# GRLV_double_Rail_v0_2b_P1.net
KiCad netlist of a schematic drawn in Altium Designer
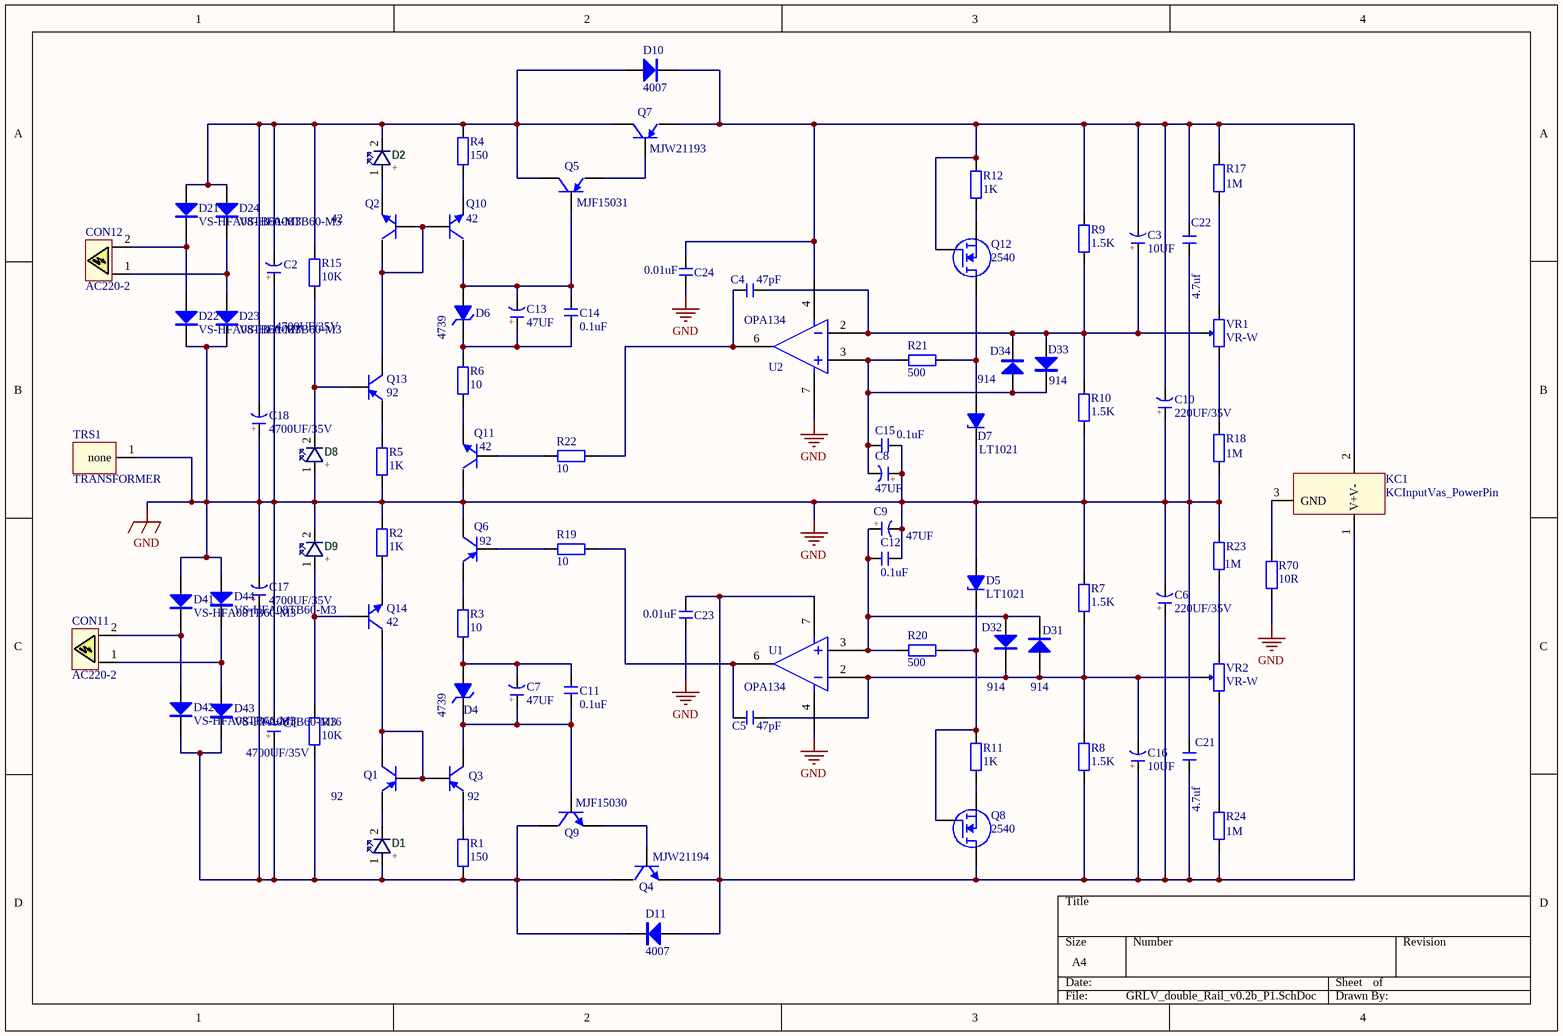
[diagram p0: GRLV_double_Rail_v0.2b_P1.SchDoc]

(export (version "E")
  (design (tool "Eeschema 10.0.6"))
  (components
    (comp (ref "C1")
      (value "4700UF/35V")
      (footprint "CAP 10*22*31.5")
      (description "直插电解电容")
      (fields (field (name "版权归属") "源创客"))
      (libsource (lib "") (part "C-CAP_1"))
    )
    (comp (ref "C2")
      (value "4700UF/35V")
      (footprint "CAP 10*22*31.5")
      (description "直插电解电容")
      (fields (field (name "版权归属") "源创客"))
      (libsource (lib "") (part "C-CAP_1"))
    )
    (comp (ref "C3")
      (value "10UF")
      (footprint "CAP 2.5*6.3*7")
      (description "直插电解电容")
      (fields (field (name "版权归属") "源创客"))
      (libsource (lib "") (part "C-CAP_1"))
    )
    (comp (ref "C4")
      (value "47pF")
      (footprint "CBB 6.3*6.3*5")
      (description "CBB电容")
      (fields (field (name "版权归属") "源创客"))
      (libsource (lib "电阻-电容-电感") (part "C-CBB"))
    )
    (comp (ref "C5")
      (value "47pF")
      (footprint "CBB 6.3*6.3*5")
      (description "CBB电容")
      (fields (field (name "版权归属") "源创客"))
      (libsource (lib "电阻-电容-电感") (part "C-CBB"))
    )
    (comp (ref "C6")
      (value "220UF/35V")
      (footprint "CAP 5.0*10*12.5")
      (description "直插电解电容")
      (fields (field (name "版权归属") "源创客"))
      (libsource (lib "") (part "C-CAP_1"))
    )
    (comp (ref "C7")
      (value "47UF")
      (footprint "CAP 3.5*8*11.5")
      (description "直插电解电容")
      (fields (field (name "版权归属") "源创客"))
      (libsource (lib "") (part "C-CAP_1"))
    )
    (comp (ref "C8")
      (value "47UF")
      (footprint "CAP 2.5*6.3*11.2")
      (description "直插电解电容")
      (fields (field (name "版权归属") "源创客"))
      (libsource (lib "电阻-电容-电感") (part "C-CAP"))
    )
    (comp (ref "C9")
      (value "47UF")
      (footprint "CAP 2.5*6.3*11.2")
      (description "直插电解电容")
      (fields (field (name "版权归属") "源创客"))
      (libsource (lib "电阻-电容-电感") (part "C-CAP"))
    )
    (comp (ref "C10")
      (value "220UF/35V")
      (footprint "CAP 5.0*10*12.5")
      (description "直插电解电容")
      (fields (field (name "版权归属") "源创客"))
      (libsource (lib "") (part "C-CAP_1"))
    )
    (comp (ref "C11")
      (value "0.1uF")
      (footprint "CBB 6.3*6.3*5")
      (description "CBB电容")
      (fields (field (name "版权归属") "源创客"))
      (libsource (lib "电阻-电容-电感") (part "C-CBB"))
    )
    (comp (ref "C12")
      (value "0.1uF")
      (footprint "CBB 6.3*6.3*5")
      (description "CBB电容")
      (fields (field (name "版权归属") "源创客"))
      (libsource (lib "电阻-电容-电感") (part "C-CBB"))
    )
    (comp (ref "C13")
      (value "47UF")
      (footprint "CAP 3.5*8*11.5")
      (description "直插电解电容")
      (fields (field (name "版权归属") "源创客"))
      (libsource (lib "") (part "C-CAP_1"))
    )
    (comp (ref "C14")
      (value "0.1uF")
      (footprint "CBB 6.3*6.3*5")
      (description "CBB电容")
      (fields (field (name "版权归属") "源创客"))
      (libsource (lib "电阻-电容-电感") (part "C-CBB"))
    )
    (comp (ref "C15")
      (value "0.1uF")
      (footprint "CBB 6.3*6.3*5")
      (description "CBB电容")
      (fields (field (name "版权归属") "源创客"))
      (libsource (lib "电阻-电容-电感") (part "C-CBB"))
    )
    (comp (ref "C16")
      (value "10UF")
      (footprint "CAP 2.5*6.3*7")
      (description "直插电解电容")
      (fields (field (name "版权归属") "源创客"))
      (libsource (lib "") (part "C-CAP_1"))
    )
    (comp (ref "C17")
      (value "4700UF/35V")
      (footprint "CAP 10*22*31.5")
      (description "直插电解电容")
      (fields (field (name "版权归属") "源创客"))
      (libsource (lib "") (part "C-CAP_1"))
    )
    (comp (ref "C18")
      (value "4700UF/35V")
      (footprint "CAP 10*22*31.5")
      (description "直插电解电容")
      (fields (field (name "版权归属") "源创客"))
      (libsource (lib "") (part "C-CAP_1"))
    )
    (comp (ref "C21")
      (value "4.7uf")
      (footprint "CBB 7.2*7.2*13")
      (description "MKS薄膜电容")
      (libsource (lib "电阻-电容-电感") (part "C-MKS"))
    )
    (comp (ref "C22")
      (value "4.7uf")
      (footprint "CBB 7.2*7.2*13")
      (description "MKS薄膜电容")
      (libsource (lib "电阻-电容-电感") (part "C-MKS"))
    )
    (comp (ref "C23")
      (value "0.01uF")
      (footprint "CBB 6.3*6.3*5")
      (description "CBB电容")
      (fields (field (name "Comment") ".01") (field (name "版权归属") "源创客"))
      (libsource (lib "电阻-电容-电感") (part "C-CBB"))
    )
    (comp (ref "C24")
      (value "0.01uF")
      (footprint "CBB 6.3*6.3*5")
      (description "CBB电容")
      (fields (field (name "Comment") ".01") (field (name "版权归属") "源创客"))
      (libsource (lib "电阻-电容-电感") (part "C-CBB"))
    )
    (comp (ref "CON11")
      (value "AC220-2")
      (footprint "HX4.0-2XS")
      (libsource (lib "Connectors") (part "AC220-2"))
    )
    (comp (ref "CON12")
      (value "AC220-2")
      (footprint "HX4.0-2XS")
      (libsource (lib "Connectors") (part "AC220-2"))
    )
    (comp (ref "D1")
      (value "+")
      (footprint "LED 3MM-R")
      (description "直插式LED")
      (libsource (lib "LED") (part "LED"))
    )
    (comp (ref "D2")
      (value "+")
      (footprint "LED 3MM-R")
      (description "直插式LED")
      (libsource (lib "LED") (part "LED"))
    )
    (comp (ref "D4")
      (value "4739")
      (footprint "DO-41")
      (description "9.1V/1W稳压管")
      (libsource (lib "二极管-整流桥") (part "1N4739"))
    )
    (comp (ref "D5")
      (value "LT1021")
      (footprint "DIP8-300_MH")
      (description "10V Precision Reference 2 Pin Config")
      (libsource (lib "电压参考") (part "LT1021-10-2P"))
    )
    (comp (ref "D6")
      (value "4739")
      (footprint "DO-41")
      (description "9.1V/1W稳压管")
      (libsource (lib "二极管-整流桥") (part "1N4739"))
    )
    (comp (ref "D7")
      (value "LT1021")
      (footprint "DIP8-300_MH")
      (description "10V Precision Reference 2 Pin Config")
      (libsource (lib "电压参考") (part "LT1021-10-2P"))
    )
    (comp (ref "D8")
      (value "+")
      (footprint "LED 3MM-R")
      (description "直插式LED")
      (libsource (lib "LED") (part "LED"))
    )
    (comp (ref "D9")
      (value "+")
      (footprint "LED 3MM-R")
      (description "直插式LED")
      (libsource (lib "LED") (part "LED"))
    )
    (comp (ref "D10")
      (value "4007")
      (footprint "DO-41")
      (description "整流二极管")
      (fields (field (name "版权归属") "源创客"))
      (libsource (lib "二极管-整流桥") (part "1N4007"))
    )
    (comp (ref "D11")
      (value "4007")
      (footprint "DO-41")
      (description "整流二极管")
      (fields (field (name "版权归属") "源创客"))
      (libsource (lib "二极管-整流桥") (part "1N4007"))
    )
    (comp (ref "D21")
      (value "VS-HFA08TB60-M3")
      (footprint "DO-15XL")
      (description "Ultrafast Soft Recovery Diado 8A 600V")
      (libsource (lib "二极管-整流桥") (part "VS-HFA08TB60-M3"))
    )
    (comp (ref "D22")
      (value "VS-HFA08TB60-M3")
      (footprint "DO-15XL")
      (description "Ultrafast Soft Recovery Diado 8A 600V")
      (libsource (lib "二极管-整流桥") (part "VS-HFA08TB60-M3"))
    )
    (comp (ref "D23")
      (value "VS-HFA08TB60-M3")
      (footprint "DO-15XL")
      (description "Ultrafast Soft Recovery Diado 8A 600V")
      (libsource (lib "二极管-整流桥") (part "VS-HFA08TB60-M3"))
    )
    (comp (ref "D24")
      (value "VS-HFA08TB60-M3")
      (footprint "DO-15XL")
      (description "Ultrafast Soft Recovery Diado 8A 600V")
      (libsource (lib "二极管-整流桥") (part "VS-HFA08TB60-M3"))
    )
    (comp (ref "D31")
      (value "914")
      (footprint "DO-35")
      (description "高速开关管 1V/0.25W")
      (libsource (lib "二极管-整流桥") (part "1N914"))
    )
    (comp (ref "D32")
      (value "914")
      (footprint "DO-35")
      (description "高速开关管 1V/0.25W")
      (libsource (lib "二极管-整流桥") (part "1N914"))
    )
    (comp (ref "D33")
      (value "914")
      (footprint "DO-35")
      (description "高速开关管 1V/0.25W")
      (libsource (lib "二极管-整流桥") (part "1N914"))
    )
    (comp (ref "D34")
      (value "914")
      (footprint "DO-35")
      (description "高速开关管 1V/0.25W")
      (libsource (lib "二极管-整流桥") (part "1N914"))
    )
    (comp (ref "D41")
      (value "VS-HFA08TB60-M3")
      (footprint "DO-15XL")
      (description "Ultrafast Soft Recovery Diado 8A 600V")
      (libsource (lib "二极管-整流桥") (part "VS-HFA08TB60-M3"))
    )
    (comp (ref "D42")
      (value "VS-HFA08TB60-M3")
      (footprint "DO-15XL")
      (description "Ultrafast Soft Recovery Diado 8A 600V")
      (libsource (lib "二极管-整流桥") (part "VS-HFA08TB60-M3"))
    )
    (comp (ref "D43")
      (value "VS-HFA08TB60-M3")
      (footprint "DO-15XL")
      (description "Ultrafast Soft Recovery Diado 8A 600V")
      (libsource (lib "二极管-整流桥") (part "VS-HFA08TB60-M3"))
    )
    (comp (ref "D44")
      (value "VS-HFA08TB60-M3")
      (footprint "DO-15XL")
      (description "Ultrafast Soft Recovery Diado 8A 600V")
      (libsource (lib "二极管-整流桥") (part "VS-HFA08TB60-M3"))
    )
    (comp (ref "KC1")
      (value "KCInputVas_PowerPin")
      (footprint "KCIn_VAS_PowerPin_M4")
      (description "King Cello Input Stage and VAS")
      (libsource (lib "KC_amp") (part "KCInputVas_PowerPin"))
    )
    (comp (ref "Q1")
      (value "92")
      (footprint "TO92A")
      (description "High Voltage PNP Transistor")
      (libsource (lib "三极管") (part "KSP92/93"))
    )
    (comp (ref "Q2")
      (value "42")
      (footprint "TO92A")
      (description "High Voltage NPN Transistor")
      (libsource (lib "三极管") (part "KSP42/43"))
    )
    (comp (ref "Q3")
      (value "92")
      (footprint "TO92A")
      (description "High Voltage PNP Transistor")
      (libsource (lib "三极管") (part "KSP92/93"))
    )
    (comp (ref "Q4")
      (value "MJW21194")
      (footprint "TO247V")
      (description "Power NPN Transistor")
      (libsource (lib "三极管") (part "MJW21194"))
    )
    (comp (ref "Q5")
      (value "MJF15031")
      (footprint "TO220V")
      (description "Power PNP Transistor")
      (libsource (lib "三极管") (part "MJF15031"))
    )
    (comp (ref "Q6")
      (value "92")
      (footprint "TO92A")
      (description "High Voltage PNP Transistor")
      (libsource (lib "三极管") (part "KSP92/93"))
    )
    (comp (ref "Q7")
      (value "MJW21193")
      (footprint "TO247V")
      (description "Power PNP Transistor")
      (libsource (lib "三极管") (part "MJW21193"))
    )
    (comp (ref "Q8")
      (value "2540")
      (footprint "TO92A")
      (description "N沟道耗尽型DMOS场效应管 400V/150ma")
      (libsource (lib "场效应管") (part "DN2540"))
    )
    (comp (ref "Q9")
      (value "MJF15030")
      (footprint "TO220V")
      (description "Power NPN Transistor")
      (libsource (lib "三极管") (part "MJF15030"))
    )
    (comp (ref "Q10")
      (value "42")
      (footprint "TO92A")
      (description "High Voltage NPN Transistor")
      (libsource (lib "三极管") (part "KSP42/43"))
    )
    (comp (ref "Q11")
      (value "42")
      (footprint "TO92A")
      (description "High Voltage NPN Transistor")
      (libsource (lib "三极管") (part "KSP42/43"))
    )
    (comp (ref "Q12")
      (value "2540")
      (footprint "TO92A")
      (description "N沟道耗尽型DMOS场效应管 400V/150ma")
      (libsource (lib "场效应管") (part "DN2540"))
    )
    (comp (ref "Q13")
      (value "92")
      (footprint "TO92A")
      (description "High Voltage PNP Transistor")
      (libsource (lib "三极管") (part "KSP92/93"))
    )
    (comp (ref "Q14")
      (value "42")
      (footprint "TO92A")
      (description "High Voltage NPN Transistor")
      (libsource (lib "三极管") (part "KSP42/43"))
    )
    (comp (ref "R1")
      (value "150")
      (footprint "RS 1/4W")
      (description "直插色环电阻")
      (fields (field (name "版权归属") "源创客"))
      (libsource (lib "电阻-电容-电感") (part "R-CRR"))
    )
    (comp (ref "R2")
      (value "1K")
      (footprint "RS 1/4W")
      (description "直插色环电阻")
      (fields (field (name "版权归属") "源创客"))
      (libsource (lib "电阻-电容-电感") (part "R-CRR"))
    )
    (comp (ref "R3")
      (value "10")
      (footprint "RS 1/4W")
      (description "直插色环电阻")
      (fields (field (name "版权归属") "源创客"))
      (libsource (lib "电阻-电容-电感") (part "R-CRR"))
    )
    (comp (ref "R4")
      (value "150")
      (footprint "RS 1/4W")
      (description "直插色环电阻")
      (fields (field (name "版权归属") "源创客"))
      (libsource (lib "电阻-电容-电感") (part "R-CRR"))
    )
    (comp (ref "R5")
      (value "1K")
      (footprint "RS 1/4W")
      (description "直插色环电阻")
      (fields (field (name "版权归属") "源创客"))
      (libsource (lib "电阻-电容-电感") (part "R-CRR"))
    )
    (comp (ref "R6")
      (value "10")
      (footprint "RS 1/4W")
      (description "直插色环电阻")
      (fields (field (name "版权归属") "源创客"))
      (libsource (lib "电阻-电容-电感") (part "R-CRR"))
    )
    (comp (ref "R7")
      (value "1.5K")
      (footprint "RS 1/4W")
      (description "直插色环电阻")
      (fields (field (name "版权归属") "源创客"))
      (libsource (lib "电阻-电容-电感") (part "R-CRR"))
    )
    (comp (ref "R8")
      (value "1.5K")
      (footprint "RS 1/4W")
      (description "直插色环电阻")
      (fields (field (name "版权归属") "源创客"))
      (libsource (lib "电阻-电容-电感") (part "R-CRR"))
    )
    (comp (ref "R9")
      (value "1.5K")
      (footprint "RS 1/4W")
      (description "直插色环电阻")
      (fields (field (name "版权归属") "源创客"))
      (libsource (lib "电阻-电容-电感") (part "R-CRR"))
    )
    (comp (ref "R10")
      (value "1.5K")
      (footprint "RS 1/4W")
      (description "直插色环电阻")
      (fields (field (name "版权归属") "源创客"))
      (libsource (lib "电阻-电容-电感") (part "R-CRR"))
    )
    (comp (ref "R11")
      (value "1K")
      (footprint "RS 1/4W")
      (description "直插色环电阻")
      (fields (field (name "版权归属") "源创客"))
      (libsource (lib "电阻-电容-电感") (part "R-CRR"))
    )
    (comp (ref "R12")
      (value "1K")
      (footprint "RS 1/4W")
      (description "直插色环电阻")
      (fields (field (name "版权归属") "源创客"))
      (libsource (lib "电阻-电容-电感") (part "R-CRR"))
    )
    (comp (ref "R15")
      (value "10K")
      (footprint "RS 1/4W")
      (description "直插色环电阻")
      (fields (field (name "版权归属") "源创客"))
      (libsource (lib "电阻-电容-电感") (part "R-CRR"))
    )
    (comp (ref "R16")
      (value "10K")
      (footprint "RS 1/4W")
      (description "直插色环电阻")
      (fields (field (name "版权归属") "源创客"))
      (libsource (lib "电阻-电容-电感") (part "R-CRR"))
    )
    (comp (ref "R17")
      (value "1M")
      (footprint "RS 1/4W")
      (description "直插色环电阻")
      (fields (field (name "版权归属") "源创客"))
      (libsource (lib "电阻-电容-电感") (part "R-CRR"))
    )
    (comp (ref "R18")
      (value "1M")
      (footprint "RS 1/4W")
      (description "直插色环电阻")
      (fields (field (name "版权归属") "源创客"))
      (libsource (lib "电阻-电容-电感") (part "R-CRR"))
    )
    (comp (ref "R19")
      (value "10")
      (footprint "RS 1/4W")
      (description "直插色环电阻")
      (fields (field (name "版权归属") "源创客"))
      (libsource (lib "电阻-电容-电感") (part "R-CRR"))
    )
    (comp (ref "R20")
      (value "500")
      (footprint "RS 1/4W")
      (description "直插色环电阻")
      (fields (field (name "版权归属") "源创客"))
      (libsource (lib "电阻-电容-电感") (part "R-CRR"))
    )
    (comp (ref "R21")
      (value "500")
      (footprint "RS 1/4W")
      (description "直插色环电阻")
      (fields (field (name "版权归属") "源创客"))
      (libsource (lib "电阻-电容-电感") (part "R-CRR"))
    )
    (comp (ref "R22")
      (value "10")
      (footprint "RS 1/4W")
      (description "直插色环电阻")
      (fields (field (name "版权归属") "源创客"))
      (libsource (lib "电阻-电容-电感") (part "R-CRR"))
    )
    (comp (ref "R23")
      (value "1M")
      (footprint "RS 1/4W")
      (description "直插色环电阻")
      (fields (field (name "版权归属") "源创客"))
      (libsource (lib "电阻-电容-电感") (part "R-CRR"))
    )
    (comp (ref "R24")
      (value "1M")
      (footprint "RS 1/4W")
      (description "直插色环电阻")
      (fields (field (name "版权归属") "源创客"))
      (libsource (lib "电阻-电容-电感") (part "R-CRR"))
    )
    (comp (ref "R70")
      (value "10R")
      (footprint "RS 1/2W")
      (description "直插色环电阻")
      (fields (field (name "版权归属") "源创客"))
      (libsource (lib "电阻-电容-电感") (part "R-CRR"))
    )
    (comp (ref "TRS1")
      (value "TRANSFORMER")
      (footprint "TRANS_BLOCK_30W_24v")
      (description "Transformer")
      (libsource (lib "KC_amp") (part "TRANSFORMER"))
    )
    (comp (ref "U1") (value "OPA134") (footprint "DIP8-300_MH") (libsource (lib "运放") (part "OPA134PA")))
    (comp (ref "U2") (value "OPA134") (footprint "DIP8-300_MH") (libsource (lib "运放") (part "OPA134PA")))
    (comp (ref "VR1")
      (value "VR-W")
      (footprint "RS 1/2W-VR")
      (description "直插可调电阻-顶调")
      (libsource (lib "电阻-电容-电感") (part "VR-W"))
    )
    (comp (ref "VR2")
      (value "VR-W")
      (footprint "RS 1/2W-VR")
      (description "直插可调电阻-顶调")
      (libsource (lib "电阻-电容-电感") (part "VR-W"))
    )
  )
  (nets
    (net (code "1") (name "GND") (class "Default")
      (node (ref "C1") (pin "2") (pinfunction "K_2") (pintype "passive"))
      (node (ref "C10") (pin "1") (pinfunction "A_1") (pintype "passive"))
      (node (ref "C12") (pin "2") (pinfunction "2_2") (pintype "passive"))
      (node (ref "C15") (pin "2") (pinfunction "2_2") (pintype "passive"))
      (node (ref "C17") (pin "2") (pinfunction "K_2") (pintype "passive"))
      (node (ref "C18") (pin "1") (pinfunction "A_1") (pintype "passive"))
      (node (ref "C2") (pin "1") (pinfunction "A_1") (pintype "passive"))
      (node (ref "C21") (pin "2") (pinfunction "2_2") (pintype "passive"))
      (node (ref "C22") (pin "1") (pinfunction "1_1") (pintype "passive"))
      (node (ref "C23") (pin "1") (pinfunction "1_1") (pintype "passive"))
      (node (ref "C24") (pin "1") (pinfunction "1_1") (pintype "passive"))
      (node (ref "C6") (pin "2") (pinfunction "K_2") (pintype "passive"))
      (node (ref "C8") (pin "1") (pinfunction "A_1") (pintype "passive"))
      (node (ref "C9") (pin "2") (pinfunction "K_2") (pintype "passive"))
      (node (ref "D22") (pin "1") (pinfunction "Cathode_1") (pintype "passive"))
      (node (ref "D23") (pin "1") (pinfunction "Cathode_1") (pintype "passive"))
      (node (ref "D41") (pin "2") (pinfunction "Anode_2") (pintype "passive"))
      (node (ref "D44") (pin "2") (pinfunction "Anode_2") (pintype "passive"))
      (node (ref "D5") (pin "4") (pinfunction "A_4") (pintype "passive"))
      (node (ref "D7") (pin "6") (pinfunction "K_6") (pintype "passive"))
      (node (ref "D8") (pin "1") (pinfunction "A_1") (pintype "passive"))
      (node (ref "D9") (pin "2") (pinfunction "K_2") (pintype "passive"))
      (node (ref "Q11") (pin "3") (pinfunction "C_3") (pintype "passive"))
      (node (ref "Q6") (pin "3") (pinfunction "C_3") (pintype "passive"))
      (node (ref "R10") (pin "1") (pinfunction "1_1") (pintype "passive"))
      (node (ref "R18") (pin "1") (pinfunction "1_1") (pintype "passive"))
      (node (ref "R2") (pin "2") (pinfunction "2_2") (pintype "passive"))
      (node (ref "R23") (pin "2") (pinfunction "2_2") (pintype "passive"))
      (node (ref "R5") (pin "1") (pinfunction "1_1") (pintype "passive"))
      (node (ref "R7") (pin "2") (pinfunction "2_2") (pintype "passive"))
      (node (ref "R70") (pin "1") (pinfunction "1_1") (pintype "passive"))
      (node (ref "TRS1") (pin "1") (pinfunction "none_1") (pintype "passive"))
      (node (ref "U1") (pin "4") (pinfunction "V-_4") (pintype "passive"))
      (node (ref "U2") (pin "7") (pinfunction "V+_7") (pintype "passive"))
    )
    (net (code "2") (name "Net-(C1-A)") (class "Default")
      (node (ref "C1") (pin "1") (pinfunction "A_1") (pintype "passive"))
      (node (ref "C17") (pin "1") (pinfunction "A_1") (pintype "passive"))
      (node (ref "D1") (pin "1") (pinfunction "A_1") (pintype "passive"))
      (node (ref "D11") (pin "2") (pinfunction "K_2") (pintype "passive"))
      (node (ref "D42") (pin "1") (pinfunction "Cathode_1") (pintype "passive"))
      (node (ref "D43") (pin "1") (pinfunction "Cathode_1") (pintype "passive"))
      (node (ref "Q4") (pin "2") (pinfunction "C_2") (pintype "passive"))
      (node (ref "Q9") (pin "2") (pinfunction "C_2") (pintype "passive"))
      (node (ref "R1") (pin "1") (pinfunction "1_1") (pintype "passive"))
      (node (ref "R16") (pin "1") (pinfunction "1_1") (pintype "passive"))
    )
    (net (code "3") (name "Net-(C3-A)") (class "Default")
      (node (ref "C3") (pin "1") (pinfunction "A_1") (pintype "passive"))
      (node (ref "C4") (pin "2") (pinfunction "2_2") (pintype "passive"))
      (node (ref "D33") (pin "1") (pinfunction "A_1") (pintype "passive"))
      (node (ref "D34") (pin "2") (pinfunction "K_2") (pintype "passive"))
      (node (ref "R10") (pin "2") (pinfunction "2_2") (pintype "passive"))
      (node (ref "R9") (pin "1") (pinfunction "1_1") (pintype "passive"))
      (node (ref "U2") (pin "2") (pinfunction "-in_2") (pintype "passive"))
      (node (ref "VR1") (pin "3") (pinfunction "3_3") (pintype "passive"))
    )
    (net (code "4") (name "Net-(C7-A)") (class "Default")
      (node (ref "C11") (pin "1") (pinfunction "1_1") (pintype "passive"))
      (node (ref "C7") (pin "1") (pinfunction "A_1") (pintype "passive"))
      (node (ref "D4") (pin "2") (pinfunction "K_2") (pintype "passive"))
      (node (ref "Q3") (pin "3") (pinfunction "C_3") (pintype "passive"))
      (node (ref "Q9") (pin "1") (pinfunction "B_1") (pintype "passive"))
    )
    (net (code "5") (name "Net-(C7-K)") (class "Default")
      (node (ref "C11") (pin "2") (pinfunction "2_2") (pintype "passive"))
      (node (ref "C7") (pin "2") (pinfunction "K_2") (pintype "passive"))
      (node (ref "D4") (pin "1") (pinfunction "A_1") (pintype "passive"))
      (node (ref "R3") (pin "1") (pinfunction "1_1") (pintype "passive"))
    )
    (net (code "6") (name "Net-(C8-K)") (class "Default")
      (node (ref "C15") (pin "1") (pinfunction "1_1") (pintype "passive"))
      (node (ref "C8") (pin "2") (pinfunction "K_2") (pintype "passive"))
      (node (ref "D33") (pin "2") (pinfunction "K_2") (pintype "passive"))
      (node (ref "D34") (pin "1") (pinfunction "A_1") (pintype "passive"))
      (node (ref "R21") (pin "1") (pinfunction "1_1") (pintype "passive"))
      (node (ref "U2") (pin "3") (pinfunction "+in_3") (pintype "passive"))
    )
    (net (code "7") (name "Net-(C9-A)") (class "Default")
      (node (ref "C12") (pin "1") (pinfunction "1_1") (pintype "passive"))
      (node (ref "C9") (pin "1") (pinfunction "A_1") (pintype "passive"))
      (node (ref "D31") (pin "2") (pinfunction "K_2") (pintype "passive"))
      (node (ref "D32") (pin "1") (pinfunction "A_1") (pintype "passive"))
      (node (ref "R20") (pin "1") (pinfunction "1_1") (pintype "passive"))
      (node (ref "U1") (pin "3") (pinfunction "+in_3") (pintype "passive"))
    )
    (net (code "8") (name "Net-(C10-K)") (class "Default")
      (node (ref "C10") (pin "2") (pinfunction "K_2") (pintype "passive"))
      (node (ref "C22") (pin "2") (pinfunction "2_2") (pintype "passive"))
      (node (ref "C24") (pin "2") (pinfunction "2_2") (pintype "passive"))
      (node (ref "C3") (pin "2") (pinfunction "K_2") (pintype "passive"))
      (node (ref "D10") (pin "2") (pinfunction "K_2") (pintype "passive"))
      (node (ref "KC1") (pin "2") (pinfunction "V-_2") (pintype "passive"))
      (node (ref "Q12") (pin "2") (pinfunction "G_2") (pintype "passive"))
      (node (ref "Q7") (pin "3") (pinfunction "E_3") (pintype "passive"))
      (node (ref "R12") (pin "2") (pinfunction "2_2") (pintype "passive"))
      (node (ref "R17") (pin "2") (pinfunction "2_2") (pintype "passive"))
      (node (ref "R9") (pin "2") (pinfunction "2_2") (pintype "passive"))
      (node (ref "U2") (pin "4") (pinfunction "V-_4") (pintype "passive"))
    )
    (net (code "9") (name "Net-(C13-A)") (class "Default")
      (node (ref "C13") (pin "1") (pinfunction "A_1") (pintype "passive"))
      (node (ref "C14") (pin "1") (pinfunction "1_1") (pintype "passive"))
      (node (ref "D6") (pin "2") (pinfunction "K_2") (pintype "passive"))
      (node (ref "R6") (pin "2") (pinfunction "2_2") (pintype "passive"))
    )
    (net (code "10") (name "Net-(C13-K)") (class "Default")
      (node (ref "C13") (pin "2") (pinfunction "K_2") (pintype "passive"))
      (node (ref "C14") (pin "2") (pinfunction "2_2") (pintype "passive"))
      (node (ref "D6") (pin "1") (pinfunction "A_1") (pintype "passive"))
      (node (ref "Q10") (pin "3") (pinfunction "C_3") (pintype "passive"))
      (node (ref "Q5") (pin "1") (pinfunction "B_1") (pintype "passive"))
    )
    (net (code "11") (name "Net-(C16-A)") (class "Default")
      (node (ref "C16") (pin "1") (pinfunction "A_1") (pintype "passive"))
      (node (ref "C21") (pin "1") (pinfunction "1_1") (pintype "passive"))
      (node (ref "C23") (pin "2") (pinfunction "2_2") (pintype "passive"))
      (node (ref "C6") (pin "1") (pinfunction "A_1") (pintype "passive"))
      (node (ref "D11") (pin "1") (pinfunction "A_1") (pintype "passive"))
      (node (ref "KC1") (pin "1") (pinfunction "V+_1") (pintype "passive"))
      (node (ref "Q4") (pin "3") (pinfunction "E_3") (pintype "passive"))
      (node (ref "Q8") (pin "3") (pinfunction "D_3") (pintype "passive"))
      (node (ref "R24") (pin "1") (pinfunction "1_1") (pintype "passive"))
      (node (ref "R8") (pin "1") (pinfunction "1_1") (pintype "passive"))
      (node (ref "U1") (pin "7") (pinfunction "V+_7") (pintype "passive"))
    )
    (net (code "12") (name "Net-(C16-K)") (class "Default")
      (node (ref "C16") (pin "2") (pinfunction "K_2") (pintype "passive"))
      (node (ref "C5") (pin "2") (pinfunction "2_2") (pintype "passive"))
      (node (ref "D31") (pin "1") (pinfunction "A_1") (pintype "passive"))
      (node (ref "D32") (pin "2") (pinfunction "K_2") (pintype "passive"))
      (node (ref "R7") (pin "1") (pinfunction "1_1") (pintype "passive"))
      (node (ref "R8") (pin "2") (pinfunction "2_2") (pintype "passive"))
      (node (ref "U1") (pin "2") (pinfunction "-in_2") (pintype "passive"))
      (node (ref "VR2") (pin "3") (pinfunction "3_3") (pintype "passive"))
    )
    (net (code "13") (name "Net-(C18-K)") (class "Default")
      (node (ref "C18") (pin "2") (pinfunction "K_2") (pintype "passive"))
      (node (ref "C2") (pin "2") (pinfunction "K_2") (pintype "passive"))
      (node (ref "D10") (pin "1") (pinfunction "A_1") (pintype "passive"))
      (node (ref "D2") (pin "2") (pinfunction "K_2") (pintype "passive"))
      (node (ref "D21") (pin "2") (pinfunction "Anode_2") (pintype "passive"))
      (node (ref "D24") (pin "2") (pinfunction "Anode_2") (pintype "passive"))
      (node (ref "Q5") (pin "2") (pinfunction "C_2") (pintype "passive"))
      (node (ref "Q7") (pin "2") (pinfunction "C_2") (pintype "passive"))
      (node (ref "R15") (pin "2") (pinfunction "2_2") (pintype "passive"))
      (node (ref "R4") (pin "2") (pinfunction "2_2") (pintype "passive"))
    )
    (net (code "14") (name "Net-(CON11-G)") (class "Default")
      (node (ref "CON11") (pin "2") (pinfunction "G_2") (pintype "passive"))
      (node (ref "D41") (pin "1") (pinfunction "Cathode_1") (pintype "passive"))
      (node (ref "D42") (pin "2") (pinfunction "Anode_2") (pintype "passive"))
    )
    (net (code "15") (name "Net-(CON11-L)") (class "Default")
      (node (ref "CON11") (pin "1") (pinfunction "L_1") (pintype "passive"))
      (node (ref "D43") (pin "2") (pinfunction "Anode_2") (pintype "passive"))
      (node (ref "D44") (pin "1") (pinfunction "Cathode_1") (pintype "passive"))
    )
    (net (code "16") (name "Net-(CON12-G)") (class "Default")
      (node (ref "CON12") (pin "2") (pinfunction "G_2") (pintype "passive"))
      (node (ref "D21") (pin "1") (pinfunction "Cathode_1") (pintype "passive"))
      (node (ref "D22") (pin "2") (pinfunction "Anode_2") (pintype "passive"))
    )
    (net (code "17") (name "Net-(CON12-L)") (class "Default")
      (node (ref "CON12") (pin "1") (pinfunction "L_1") (pintype "passive"))
      (node (ref "D23") (pin "2") (pinfunction "Anode_2") (pintype "passive"))
      (node (ref "D24") (pin "1") (pinfunction "Cathode_1") (pintype "passive"))
    )
    (net (code "18") (name "Net-(D1-K)") (class "Default")
      (node (ref "D1") (pin "2") (pinfunction "K_2") (pintype "passive"))
      (node (ref "Q1") (pin "1") (pinfunction "E_1") (pintype "passive"))
    )
    (net (code "19") (name "Net-(D2-A)") (class "Default")
      (node (ref "D2") (pin "1") (pinfunction "A_1") (pintype "passive"))
      (node (ref "Q2") (pin "1") (pinfunction "E_1") (pintype "passive"))
    )
    (net (code "20") (name "Net-(D5-K)") (class "Default")
      (node (ref "D5") (pin "6") (pinfunction "K_6") (pintype "passive"))
      (node (ref "Q8") (pin "2") (pinfunction "G_2") (pintype "passive"))
      (node (ref "R11") (pin "2") (pinfunction "2_2") (pintype "passive"))
      (node (ref "R20") (pin "2") (pinfunction "2_2") (pintype "passive"))
    )
    (net (code "21") (name "Net-(D7-A)") (class "Default")
      (node (ref "D7") (pin "4") (pinfunction "A_4") (pintype "passive"))
      (node (ref "Q12") (pin "3") (pinfunction "D_3") (pintype "passive"))
      (node (ref "R21") (pin "2") (pinfunction "2_2") (pintype "passive"))
    )
    (net (code "22") (name "Net-(D8-K)") (class "Default")
      (node (ref "D8") (pin "2") (pinfunction "K_2") (pintype "passive"))
      (node (ref "Q13") (pin "2") (pinfunction "B_2") (pintype "passive"))
      (node (ref "R15") (pin "1") (pinfunction "1_1") (pintype "passive"))
    )
    (net (code "23") (name "Net-(D9-A)") (class "Default")
      (node (ref "D9") (pin "1") (pinfunction "A_1") (pintype "passive"))
      (node (ref "Q14") (pin "2") (pinfunction "B_2") (pintype "passive"))
      (node (ref "R16") (pin "2") (pinfunction "2_2") (pintype "passive"))
    )
    (net (code "24") (name "Net-(KC1-GND)") (class "Default")
      (node (ref "KC1") (pin "3") (pinfunction "GND_3") (pintype "passive"))
      (node (ref "R70") (pin "2") (pinfunction "2_2") (pintype "passive"))
    )
    (net (code "25") (name "Net-(Q1-B)") (class "Default")
      (node (ref "Q1") (pin "2") (pinfunction "B_2") (pintype "passive"))
      (node (ref "Q1") (pin "3") (pinfunction "C_3") (pintype "passive"))
      (node (ref "Q14") (pin "3") (pinfunction "C_3") (pintype "passive"))
      (node (ref "Q3") (pin "2") (pinfunction "B_2") (pintype "passive"))
    )
    (net (code "26") (name "Net-(Q3-E)") (class "Default")
      (node (ref "Q3") (pin "1") (pinfunction "E_1") (pintype "passive"))
      (node (ref "R1") (pin "2") (pinfunction "2_2") (pintype "passive"))
    )
    (net (code "27") (name "Net-(Q4-B)") (class "Default")
      (node (ref "Q4") (pin "1") (pinfunction "B_1") (pintype "passive"))
      (node (ref "Q9") (pin "3") (pinfunction "E_3") (pintype "passive"))
    )
    (net (code "28") (name "Net-(Q5-E)") (class "Default")
      (node (ref "Q5") (pin "3") (pinfunction "E_3") (pintype "passive"))
      (node (ref "Q7") (pin "1") (pinfunction "B_1") (pintype "passive"))
    )
    (net (code "29") (name "Net-(Q6-B)") (class "Default")
      (node (ref "Q6") (pin "2") (pinfunction "B_2") (pintype "passive"))
      (node (ref "R19") (pin "1") (pinfunction "1_1") (pintype "passive"))
    )
    (net (code "30") (name "Net-(Q6-E)") (class "Default")
      (node (ref "Q6") (pin "1") (pinfunction "E_1") (pintype "passive"))
      (node (ref "R3") (pin "2") (pinfunction "2_2") (pintype "passive"))
    )
    (net (code "31") (name "Net-(Q8-S)") (class "Default")
      (node (ref "Q8") (pin "1") (pinfunction "S_1") (pintype "passive"))
      (node (ref "R11") (pin "1") (pinfunction "1_1") (pintype "passive"))
    )
    (net (code "32") (name "Net-(Q10-B)") (class "Default")
      (node (ref "Q10") (pin "2") (pinfunction "B_2") (pintype "passive"))
      (node (ref "Q13") (pin "3") (pinfunction "C_3") (pintype "passive"))
      (node (ref "Q2") (pin "2") (pinfunction "B_2") (pintype "passive"))
      (node (ref "Q2") (pin "3") (pinfunction "C_3") (pintype "passive"))
    )
    (net (code "33") (name "Net-(Q10-E)") (class "Default")
      (node (ref "Q10") (pin "1") (pinfunction "E_1") (pintype "passive"))
      (node (ref "R4") (pin "1") (pinfunction "1_1") (pintype "passive"))
    )
    (net (code "34") (name "Net-(Q11-B)") (class "Default")
      (node (ref "Q11") (pin "2") (pinfunction "B_2") (pintype "passive"))
      (node (ref "R22") (pin "1") (pinfunction "1_1") (pintype "passive"))
    )
    (net (code "35") (name "Net-(Q11-E)") (class "Default")
      (node (ref "Q11") (pin "1") (pinfunction "E_1") (pintype "passive"))
      (node (ref "R6") (pin "1") (pinfunction "1_1") (pintype "passive"))
    )
    (net (code "36") (name "Net-(Q12-S)") (class "Default")
      (node (ref "Q12") (pin "1") (pinfunction "S_1") (pintype "passive"))
      (node (ref "R12") (pin "1") (pinfunction "1_1") (pintype "passive"))
    )
    (net (code "37") (name "Net-(Q13-E)") (class "Default")
      (node (ref "Q13") (pin "1") (pinfunction "E_1") (pintype "passive"))
      (node (ref "R5") (pin "2") (pinfunction "2_2") (pintype "passive"))
    )
    (net (code "38") (name "Net-(Q14-E)") (class "Default")
      (node (ref "Q14") (pin "1") (pinfunction "E_1") (pintype "passive"))
      (node (ref "R2") (pin "1") (pinfunction "1_1") (pintype "passive"))
    )
    (net (code "39") (name "Net-(R17-Pad1)") (class "Default")
      (node (ref "R17") (pin "1") (pinfunction "1_1") (pintype "passive"))
      (node (ref "VR1") (pin "2") (pinfunction "2_2") (pintype "passive"))
    )
    (net (code "40") (name "Net-(R18-Pad2)") (class "Default")
      (node (ref "R18") (pin "2") (pinfunction "2_2") (pintype "passive"))
      (node (ref "VR1") (pin "1") (pinfunction "1_1") (pintype "passive"))
    )
    (net (code "41") (name "Net-(R23-Pad1)") (class "Default")
      (node (ref "R23") (pin "1") (pinfunction "1_1") (pintype "passive"))
      (node (ref "VR2") (pin "2") (pinfunction "2_2") (pintype "passive"))
    )
    (net (code "42") (name "Net-(R24-Pad2)") (class "Default")
      (node (ref "R24") (pin "2") (pinfunction "2_2") (pintype "passive"))
      (node (ref "VR2") (pin "1") (pinfunction "1_1") (pintype "passive"))
    )
    (net (code "43") (name "Net-(U1-out)") (class "Default")
      (node (ref "C5") (pin "1") (pinfunction "1_1") (pintype "passive"))
      (node (ref "R19") (pin "2") (pinfunction "2_2") (pintype "passive"))
      (node (ref "U1") (pin "6") (pinfunction "out_6") (pintype "passive"))
    )
    (net (code "44") (name "Net-(U2-out)") (class "Default")
      (node (ref "C4") (pin "1") (pinfunction "1_1") (pintype "passive"))
      (node (ref "R22") (pin "2") (pinfunction "2_2") (pintype "passive"))
      (node (ref "U2") (pin "6") (pinfunction "out_6") (pintype "passive"))
    )
  )
)
